# Gate_Driver_3.net
KiCad netlist of a schematic drawn in Altium Designer
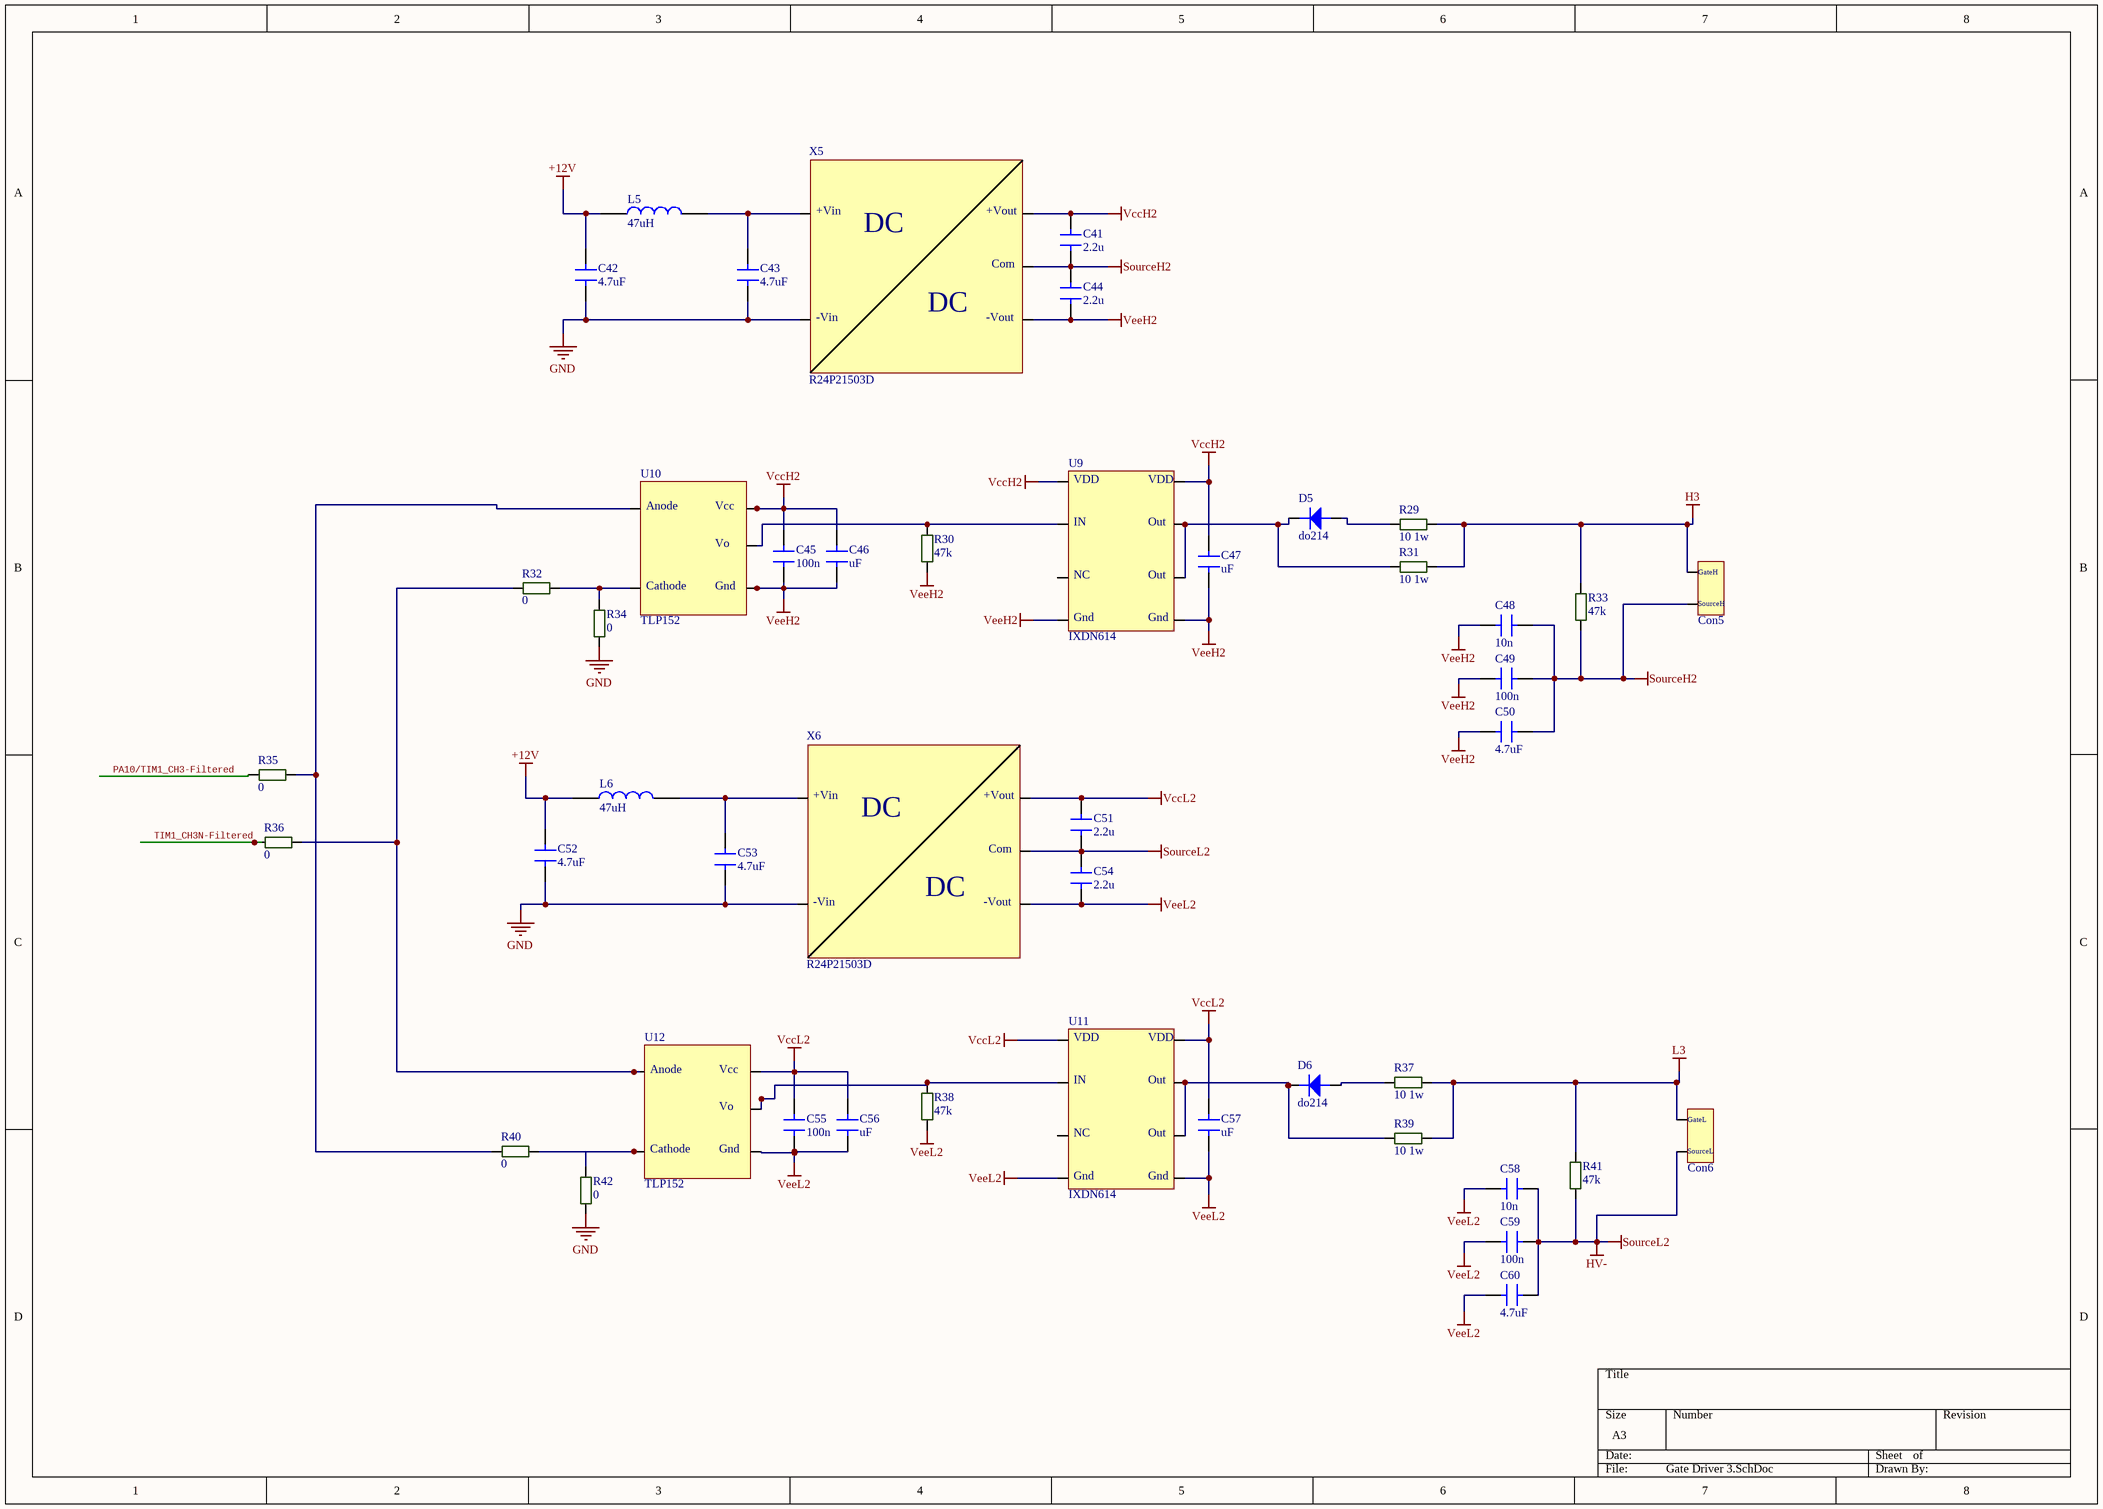
[diagram p0: Gate Driver 3.SchDoc]

(export (version "E")
  (design (tool "Eeschema 10.0.6"))
  (components
    (comp (ref "C41")
      (value "2.2u")
      (footprint "C-0805")
      (libsource (lib "Gate Driver Board") (part "C-0805"))
    )
    (comp (ref "C42")
      (value "4.7uF")
      (footprint "C-1206")
      (description "MLCC (3216) 1206 4.7uF 50VDC ±10% X7R")
      (fields (field (name "ÖZDISAN PART NUMBER") "CL31B475KBHNNNE") (field (name "MANUFACTURER") "SAMSUNG"))
      (libsource (lib "Gate Driver Board") (part "Cap1206"))
    )
    (comp (ref "C43")
      (value "4.7uF")
      (footprint "C-1206")
      (description "MLCC (3216) 1206 4.7uF 50VDC ±10% X7R")
      (fields (field (name "ÖZDISAN PART NUMBER") "CL31B475KBHNNNE") (field (name "MANUFACTURER") "SAMSUNG"))
      (libsource (lib "Gate Driver Board") (part "Cap1206"))
    )
    (comp (ref "C44")
      (value "2.2u")
      (footprint "C-0805")
      (libsource (lib "Gate Driver Board") (part "C-0805"))
    )
    (comp (ref "C45")
      (value "100n")
      (footprint "C-0805")
      (libsource (lib "Gate Driver Board") (part "C-0805"))
    )
    (comp (ref "C46") (value "uF") (footprint "C-1206") (libsource (lib "Gate Driver Board") (part "C-1206")))
    (comp (ref "C47") (value "uF") (footprint "C-1206") (libsource (lib "Gate Driver Board") (part "C-1206")))
    (comp (ref "C48")
      (value "10n")
      (footprint "C-0805")
      (libsource (lib "Gate Driver Board") (part "C-0805"))
    )
    (comp (ref "C49")
      (value "100n")
      (footprint "C-0805")
      (libsource (lib "Gate Driver Board") (part "C-0805"))
    )
    (comp (ref "C50")
      (value "4.7uF")
      (footprint "C-1206")
      (description "MLCC (3216) 1206 4.7uF 50VDC ±10% X7R")
      (fields (field (name "ÖZDISAN PART NUMBER") " CL31B475KBHNNNE") (field (name "MANUFACTURER") "SAMSUNG"))
      (libsource (lib "Gate Driver Board") (part "Cap1206"))
    )
    (comp (ref "C51")
      (value "2.2u")
      (footprint "C-0805")
      (libsource (lib "Gate Driver Board") (part "C-0805"))
    )
    (comp (ref "C52")
      (value "4.7uF")
      (footprint "C-1206")
      (description "MLCC (3216) 1206 4.7uF 50VDC ±10% X7R")
      (fields (field (name "ÖZDISAN PART NUMBER") "CL31B475KBHNNNE") (field (name "MANUFACTURER") "SAMSUNG"))
      (libsource (lib "Gate Driver Board") (part "Cap1206"))
    )
    (comp (ref "C53")
      (value "4.7uF")
      (footprint "C-1206")
      (description "MLCC (3216) 1206 4.7uF 50VDC ±10% X7R")
      (fields (field (name "ÖZDISAN PART NUMBER") " CL31B475KBHNNNE") (field (name "MANUFACTURER") "SAMSUNG"))
      (libsource (lib "Gate Driver Board") (part "Cap1206"))
    )
    (comp (ref "C54")
      (value "2.2u")
      (footprint "C-0805")
      (libsource (lib "Gate Driver Board") (part "C-0805"))
    )
    (comp (ref "C55")
      (value "100n")
      (footprint "C-0805")
      (libsource (lib "Gate Driver Board") (part "C-0805"))
    )
    (comp (ref "C56") (value "uF") (footprint "C-1206") (libsource (lib "Gate Driver Board") (part "C-1206")))
    (comp (ref "C57") (value "uF") (footprint "C-1206") (libsource (lib "Gate Driver Board") (part "C-1206")))
    (comp (ref "C58")
      (value "10n")
      (footprint "C-0805")
      (libsource (lib "Gate Driver Board") (part "C-0805"))
    )
    (comp (ref "C59")
      (value "100n")
      (footprint "C-0805")
      (libsource (lib "Gate Driver Board") (part "C-0805"))
    )
    (comp (ref "C60")
      (value "4.7uF")
      (footprint "C-1206")
      (description "MLCC (3216) 1206 4.7uF 50VDC ±10% X7R")
      (fields (field (name "ÖZDISAN PART NUMBER") "CL31B475KBHNNNE") (field (name "MANUFACTURER") "SAMSUNG"))
      (libsource (lib "Gate Driver Board") (part "Cap1206"))
    )
    (comp (ref "Con5")
      (value "Connector2_1")
      (footprint "Conn")
      (libsource (lib "Gate Driver Board") (part "Connector2_1"))
    )
    (comp (ref "Con6")
      (value "Connector2_2")
      (footprint "Conn")
      (libsource (lib "Gate Driver Board") (part "Connector2_2"))
    )
    (comp (ref "D5")
      (value "do214")
      (footprint "DO-214AC")
      (description "DIODE FAST SWITCHING Single 150mA 75V SMT SOD323")
      (libsource (lib "Gate Driver Board") (part "do214"))
    )
    (comp (ref "D6")
      (value "do214")
      (footprint "DO-214AC")
      (description "DIODE FAST SWITCHING Single 150mA 75V SMT SOD323")
      (libsource (lib "Gate Driver Board") (part "do214"))
    )
    (comp (ref "L5")
      (value "47uH")
      (footprint "WE-TPC_282892")
      (libsource (lib "Gate Driver Board") (part "inductor"))
    )
    (comp (ref "L6")
      (value "47uH")
      (footprint "WE-TPC_282892")
      (libsource (lib "Gate Driver Board") (part "inductor"))
    )
    (comp (ref "R29")
      (value "10 1w")
      (footprint "R-2512")
      (libsource (lib "Gate Driver Board") (part "R-2512"))
    )
    (comp (ref "R30")
      (value "47k")
      (footprint "R-0805")
      (description "RES.(2012) 0805 47K Ohms 5% 1/8W-S 100PPM")
      (fields (field (name "MANUFACTURER") "ROYALOHM") (field (name "ÖZDISAN PART NUMBER") "0805S8J0473T5E"))
      (libsource (lib "Gate Driver Board") (part "Res0805"))
    )
    (comp (ref "R31")
      (value "10 1w")
      (footprint "R-2512")
      (libsource (lib "Gate Driver Board") (part "R-2512"))
    )
    (comp (ref "R32")
      (value "0")
      (footprint "R-0805")
      (description "RES.(2012) 0805 0 Ohms 5% 1/8W-S 800PPM")
      (fields (field (name "MANUFACTURER") "ROYALOHM") (field (name "ÖZDISAN PART NUMBER") "0805S8J0000T5E"))
      (libsource (lib "Gate Driver Board") (part "Res0805"))
    )
    (comp (ref "R33")
      (value "47k")
      (footprint "R-0805")
      (description "RES.(2012) 0805 47K Ohms 5% 1/8W-S 100PPM")
      (fields (field (name "ÖZDISAN PART NUMBER") "0805S8J0473T5E") (field (name "MANUFACTURER") "ROYALOHM"))
      (libsource (lib "Gate Driver Board") (part "Res0805"))
    )
    (comp (ref "R34")
      (value "0")
      (footprint "R-0805")
      (description "RES.(2012) 0805 0 Ohms 5% 1/8W-S 800PPM")
      (fields (field (name "MANUFACTURER") "ROYALOHM") (field (name "ÖZDISAN PART NUMBER") "0805S8J0000T5E"))
      (libsource (lib "Gate Driver Board") (part "Res0805"))
    )
    (comp (ref "R35")
      (value "0")
      (footprint "R-0805")
      (description "RES.(2012) 0805 0 Ohms 5% 1/8W-S 800PPM")
      (fields (field (name "MANUFACTURER") "ROYALOHM") (field (name "ÖZDISAN PART NUMBER") "0805S8J0000T5E"))
      (libsource (lib "Gate Driver Board") (part "Res0805"))
    )
    (comp (ref "R36")
      (value "0")
      (footprint "R-0805")
      (description "RES.(2012) 0805 0 Ohms 5% 1/8W-S 800PPM")
      (fields (field (name "MANUFACTURER") "ROYALOHM") (field (name "ÖZDISAN PART NUMBER") "0805S8J0000T5E"))
      (libsource (lib "Gate Driver Board") (part "Res0805"))
    )
    (comp (ref "R37")
      (value "10 1w")
      (footprint "R-2512")
      (libsource (lib "Gate Driver Board") (part "R-2512"))
    )
    (comp (ref "R38")
      (value "47k")
      (footprint "R-0805")
      (description "RES.(2012) 0805 47K Ohms 5% 1/8W-S 100PPM")
      (fields (field (name "ÖZDISAN PART NUMBER") "0805S8J0473T5E") (field (name "MANUFACTURER") "ROYALOHM"))
      (libsource (lib "Gate Driver Board") (part "Res0805"))
    )
    (comp (ref "R39")
      (value "10 1w")
      (footprint "R-2512")
      (libsource (lib "Gate Driver Board") (part "R-2512"))
    )
    (comp (ref "R40")
      (value "0")
      (footprint "R-0805")
      (description "RES.(2012) 0805 0 Ohms 5% 1/8W-S 800PPM")
      (fields (field (name "MANUFACTURER") "ROYALOHM") (field (name "ÖZDISAN PART NUMBER") "0805S8J0000T5E"))
      (libsource (lib "Gate Driver Board") (part "Res0805"))
    )
    (comp (ref "R41")
      (value "47k")
      (footprint "R-0805")
      (description "RES.(2012) 0805 47K Ohms 5% 1/8W-S 100PPM")
      (fields (field (name "ÖZDISAN PART NUMBER") "0805S8J0473T5E") (field (name "MANUFACTURER") "ROYALOHM"))
      (libsource (lib "Gate Driver Board") (part "Res0805"))
    )
    (comp (ref "R42")
      (value "0")
      (footprint "R-0805")
      (description "RES.(2012) 0805 0 Ohms 5% 1/8W-S 800PPM")
      (fields (field (name "MANUFACTURER") "ROYALOHM") (field (name "ÖZDISAN PART NUMBER") "0805S8J0000T5E"))
      (libsource (lib "Gate Driver Board") (part "Res0805"))
    )
    (comp (ref "U9")
      (value "IXDN614")
      (footprint "FAN3122 Soic8")
      (description "14A 8SOIC EXP MTL NON INVERTING")
      (fields
        (field (name "MANUFACTURER") "Ixys Clare")
        (field (name "MANUFACTURER PART NUMBER") "IXDN614SITR")
      )
      (libsource (lib "Gate Driver Board") (part "IXDN614SITR"))
    )
    (comp (ref "U10")
      (value "TLP152")
      (footprint "TLP152")
      (description "OPTOISO 3.75KV GATE DRIVER 6SO-5")
      (fields
        (field (name "MANUFACTURER") "Toshiba")
        (field (name "MANUFACTURER PART NUMBER") "TLP152(TPL,E")
      )
      (libsource (lib "Gate Driver Board") (part "TLP152(TPL,E"))
    )
    (comp (ref "U11")
      (value "IXDN614")
      (footprint "FAN3122 Soic8")
      (description "14A 8SOIC EXP MTL NON INVERTING")
      (fields
        (field (name "MANUFACTURER") "Ixys Clare")
        (field (name "MANUFACTURER PART NUMBER") "IXDN614SITR")
      )
      (libsource (lib "Gate Driver Board") (part "IXDN614SITR"))
    )
    (comp (ref "U12")
      (value "TLP152")
      (footprint "TLP152")
      (description "OPTOISO 3.75KV GATE DRIVER 6SO-5")
      (fields
        (field (name "MANUFACTURER") "Toshiba")
        (field (name "MANUFACTURER PART NUMBER") "TLP152(TPL,E")
      )
      (libsource (lib "Gate Driver Board") (part "TLP152(TPL,E"))
    )
    (comp (ref "X5")
      (value "R24P21503D")
      (footprint "SIP7")
      (fields (field (name "MANUFACTURER") "Recom"))
      (libsource (lib "Gate Driver Board") (part "R24P21503D"))
    )
    (comp (ref "X6")
      (value "R24P21503D")
      (footprint "SIP7")
      (fields (field (name "MANUFACTURER") "Recom"))
      (libsource (lib "Gate Driver Board") (part "R24P21503D"))
    )
  )
  (nets
    (net (code "1") (name "+12V") (class "Default")
      (node (ref "C42") (pin "2") (pinfunction "2_2") (pintype "passive"))
      (node (ref "C52") (pin "2") (pinfunction "2_2") (pintype "passive"))
      (node (ref "L5") (pin "1") (pinfunction "1_1") (pintype "passive"))
      (node (ref "L6") (pin "1") (pinfunction "1_1") (pintype "passive"))
    )
    (net (code "2") (name "/PA10{slash}TIM1_CH3-Filtered") (class "Default")
      (node (ref "R35") (pin "1") (pinfunction "1_1") (pintype "passive"))
    )
    (net (code "3") (name "/TIM1_CH3N-Filtered") (class "Default")
      (node (ref "R36") (pin "1") (pinfunction "1_1") (pintype "passive"))
    )
    (net (code "4") (name "GND") (class "Default")
      (node (ref "C42") (pin "1") (pinfunction "1_1") (pintype "passive"))
      (node (ref "C43") (pin "1") (pinfunction "1_1") (pintype "passive"))
      (node (ref "C52") (pin "1") (pinfunction "1_1") (pintype "passive"))
      (node (ref "C53") (pin "1") (pinfunction "1_1") (pintype "passive"))
      (node (ref "R34") (pin "1") (pinfunction "1_1") (pintype "passive"))
      (node (ref "R42") (pin "1") (pinfunction "1_1") (pintype "passive"))
      (node (ref "X5") (pin "2") (pinfunction "2_2") (pintype "passive"))
      (node (ref "X6") (pin "2") (pinfunction "2_2") (pintype "passive"))
    )
    (net (code "5") (name "H3") (class "Default")
      (node (ref "Con5") (pin "1") (pinfunction "1_1") (pintype "passive"))
      (node (ref "R29") (pin "2") (pinfunction "2_2") (pintype "passive"))
      (node (ref "R31") (pin "2") (pinfunction "2_2") (pintype "passive"))
      (node (ref "R33") (pin "2") (pinfunction "2_2") (pintype "passive"))
    )
    (net (code "6") (name "HV-") (class "Default")
      (node (ref "C51") (pin "1") (pinfunction "1_1") (pintype "passive"))
      (node (ref "C54") (pin "2") (pinfunction "2_2") (pintype "passive"))
      (node (ref "C58") (pin "1") (pinfunction "1_1") (pintype "passive"))
      (node (ref "C59") (pin "1") (pinfunction "1_1") (pintype "passive"))
      (node (ref "C60") (pin "2") (pinfunction "2_2") (pintype "passive"))
      (node (ref "Con6") (pin "2") (pinfunction "2_2") (pintype "passive"))
      (node (ref "R41") (pin "1") (pinfunction "1_1") (pintype "passive"))
      (node (ref "X6") (pin "6") (pinfunction "6_6") (pintype "passive"))
    )
    (net (code "7") (name "L3") (class "Default")
      (node (ref "Con6") (pin "1") (pinfunction "1_1") (pintype "passive"))
      (node (ref "R37") (pin "2") (pinfunction "2_2") (pintype "passive"))
      (node (ref "R39") (pin "2") (pinfunction "2_2") (pintype "passive"))
      (node (ref "R41") (pin "2") (pinfunction "2_2") (pintype "passive"))
    )
    (net (code "8") (name "Net-(C43-Pad2)") (class "Default")
      (node (ref "C43") (pin "2") (pinfunction "2_2") (pintype "passive"))
      (node (ref "L5") (pin "2") (pinfunction "2_2") (pintype "passive"))
      (node (ref "X5") (pin "1") (pinfunction "1_1") (pintype "passive"))
    )
    (net (code "9") (name "Net-(C53-Pad2)") (class "Default")
      (node (ref "C53") (pin "2") (pinfunction "2_2") (pintype "passive"))
      (node (ref "L6") (pin "2") (pinfunction "2_2") (pintype "passive"))
      (node (ref "X6") (pin "1") (pinfunction "1_1") (pintype "passive"))
    )
    (net (code "10") (name "Net-(D5-Pada)") (class "Default")
      (node (ref "D5") (pin "a") (pinfunction "a_a") (pintype "passive"))
      (node (ref "R29") (pin "1") (pinfunction "1_1") (pintype "passive"))
    )
    (net (code "11") (name "Net-(D5-Padk)") (class "Default")
      (node (ref "D5") (pin "k") (pinfunction "k_k") (pintype "passive"))
      (node (ref "R31") (pin "1") (pinfunction "1_1") (pintype "passive"))
      (node (ref "U9") (pin "6") (pinfunction "6_6") (pintype "passive"))
      (node (ref "U9") (pin "7") (pinfunction "7_7") (pintype "passive"))
    )
    (net (code "12") (name "Net-(D6-Pada)") (class "Default")
      (node (ref "D6") (pin "a") (pinfunction "a_a") (pintype "passive"))
      (node (ref "R37") (pin "1") (pinfunction "1_1") (pintype "passive"))
    )
    (net (code "13") (name "Net-(D6-Padk)") (class "Default")
      (node (ref "D6") (pin "k") (pinfunction "k_k") (pintype "passive"))
      (node (ref "R39") (pin "1") (pinfunction "1_1") (pintype "passive"))
      (node (ref "U11") (pin "6") (pinfunction "6_6") (pintype "passive"))
      (node (ref "U11") (pin "7") (pinfunction "7_7") (pintype "passive"))
    )
    (net (code "14") (name "Net-(R30-Pad2)") (class "Default")
      (node (ref "R30") (pin "2") (pinfunction "2_2") (pintype "passive"))
      (node (ref "U10") (pin "4") (pinfunction "4_4") (pintype "passive"))
      (node (ref "U9") (pin "2") (pinfunction "2_2") (pintype "passive"))
    )
    (net (code "15") (name "Net-(R32-Pad1)") (class "Default")
      (node (ref "R32") (pin "1") (pinfunction "1_1") (pintype "passive"))
      (node (ref "R36") (pin "2") (pinfunction "2_2") (pintype "passive"))
      (node (ref "U12") (pin "1") (pinfunction "1_1") (pintype "passive"))
    )
    (net (code "16") (name "Net-(R32-Pad2)") (class "Default")
      (node (ref "R32") (pin "2") (pinfunction "2_2") (pintype "passive"))
      (node (ref "R34") (pin "2") (pinfunction "2_2") (pintype "passive"))
      (node (ref "U10") (pin "2") (pinfunction "2_2") (pintype "passive"))
    )
    (net (code "17") (name "Net-(R35-Pad2)") (class "Default")
      (node (ref "R35") (pin "2") (pinfunction "2_2") (pintype "passive"))
      (node (ref "R40") (pin "1") (pinfunction "1_1") (pintype "passive"))
      (node (ref "U10") (pin "1") (pinfunction "1_1") (pintype "passive"))
    )
    (net (code "18") (name "Net-(R38-Pad2)") (class "Default")
      (node (ref "R38") (pin "2") (pinfunction "2_2") (pintype "passive"))
      (node (ref "U11") (pin "2") (pinfunction "2_2") (pintype "passive"))
      (node (ref "U12") (pin "4") (pinfunction "4_4") (pintype "passive"))
    )
    (net (code "19") (name "Net-(R40-Pad2)") (class "Default")
      (node (ref "R40") (pin "2") (pinfunction "2_2") (pintype "passive"))
      (node (ref "R42") (pin "2") (pinfunction "2_2") (pintype "passive"))
      (node (ref "U12") (pin "2") (pinfunction "2_2") (pintype "passive"))
    )
    (net (code "20") (name "SourceH2") (class "Default")
      (node (ref "C41") (pin "1") (pinfunction "1_1") (pintype "passive"))
      (node (ref "C44") (pin "2") (pinfunction "2_2") (pintype "passive"))
      (node (ref "C48") (pin "1") (pinfunction "1_1") (pintype "passive"))
      (node (ref "C49") (pin "1") (pinfunction "1_1") (pintype "passive"))
      (node (ref "C50") (pin "2") (pinfunction "2_2") (pintype "passive"))
      (node (ref "Con5") (pin "2") (pinfunction "2_2") (pintype "passive"))
      (node (ref "R33") (pin "1") (pinfunction "1_1") (pintype "passive"))
      (node (ref "X5") (pin "6") (pinfunction "6_6") (pintype "passive"))
    )
    (net (code "21") (name "VccH2") (class "Default")
      (node (ref "C41") (pin "2") (pinfunction "2_2") (pintype "passive"))
      (node (ref "C45") (pin "2") (pinfunction "2_2") (pintype "passive"))
      (node (ref "C46") (pin "2") (pinfunction "2_2") (pintype "passive"))
      (node (ref "C47") (pin "2") (pinfunction "2_2") (pintype "passive"))
      (node (ref "U10") (pin "5") (pinfunction "5_5") (pintype "passive"))
      (node (ref "U9") (pin "1") (pinfunction "1_1") (pintype "passive"))
      (node (ref "U9") (pin "8") (pinfunction "8_8") (pintype "passive"))
      (node (ref "X5") (pin "7") (pinfunction "7_7") (pintype "passive"))
    )
    (net (code "22") (name "VccL2") (class "Default")
      (node (ref "C51") (pin "2") (pinfunction "2_2") (pintype "passive"))
      (node (ref "C55") (pin "2") (pinfunction "2_2") (pintype "passive"))
      (node (ref "C56") (pin "2") (pinfunction "2_2") (pintype "passive"))
      (node (ref "C57") (pin "2") (pinfunction "2_2") (pintype "passive"))
      (node (ref "U11") (pin "1") (pinfunction "1_1") (pintype "passive"))
      (node (ref "U11") (pin "8") (pinfunction "8_8") (pintype "passive"))
      (node (ref "U12") (pin "5") (pinfunction "5_5") (pintype "passive"))
      (node (ref "X6") (pin "7") (pinfunction "7_7") (pintype "passive"))
    )
    (net (code "23") (name "VeeH2") (class "Default")
      (node (ref "C44") (pin "1") (pinfunction "1_1") (pintype "passive"))
      (node (ref "C45") (pin "1") (pinfunction "1_1") (pintype "passive"))
      (node (ref "C46") (pin "1") (pinfunction "1_1") (pintype "passive"))
      (node (ref "C47") (pin "1") (pinfunction "1_1") (pintype "passive"))
      (node (ref "C48") (pin "2") (pinfunction "2_2") (pintype "passive"))
      (node (ref "C49") (pin "2") (pinfunction "2_2") (pintype "passive"))
      (node (ref "C50") (pin "1") (pinfunction "1_1") (pintype "passive"))
      (node (ref "R30") (pin "1") (pinfunction "1_1") (pintype "passive"))
      (node (ref "U10") (pin "3") (pinfunction "3_3") (pintype "passive"))
      (node (ref "U9") (pin "4") (pinfunction "4_4") (pintype "passive"))
      (node (ref "U9") (pin "5") (pinfunction "5_5") (pintype "passive"))
      (node (ref "X5") (pin "5") (pinfunction "5_5") (pintype "passive"))
    )
    (net (code "24") (name "VeeL2") (class "Default")
      (node (ref "C54") (pin "1") (pinfunction "1_1") (pintype "passive"))
      (node (ref "C55") (pin "1") (pinfunction "1_1") (pintype "passive"))
      (node (ref "C56") (pin "1") (pinfunction "1_1") (pintype "passive"))
      (node (ref "C57") (pin "1") (pinfunction "1_1") (pintype "passive"))
      (node (ref "C58") (pin "2") (pinfunction "2_2") (pintype "passive"))
      (node (ref "C59") (pin "2") (pinfunction "2_2") (pintype "passive"))
      (node (ref "C60") (pin "1") (pinfunction "1_1") (pintype "passive"))
      (node (ref "R38") (pin "1") (pinfunction "1_1") (pintype "passive"))
      (node (ref "U11") (pin "4") (pinfunction "4_4") (pintype "passive"))
      (node (ref "U11") (pin "5") (pinfunction "5_5") (pintype "passive"))
      (node (ref "U12") (pin "3") (pinfunction "3_3") (pintype "passive"))
      (node (ref "X6") (pin "5") (pinfunction "5_5") (pintype "passive"))
    )
    (net (code "25") (name "unconnected-(U9-Pad3)") (class "Default")
      (node (ref "U9") (pin "3") (pinfunction "3_3") (pintype "passive"))
    )
    (net (code "26") (name "unconnected-(U11-Pad3)") (class "Default")
      (node (ref "U11") (pin "3") (pinfunction "3_3") (pintype "passive"))
    )
  )
)
